# Notification.net
KiCad netlist of a schematic drawn in Altium Designer
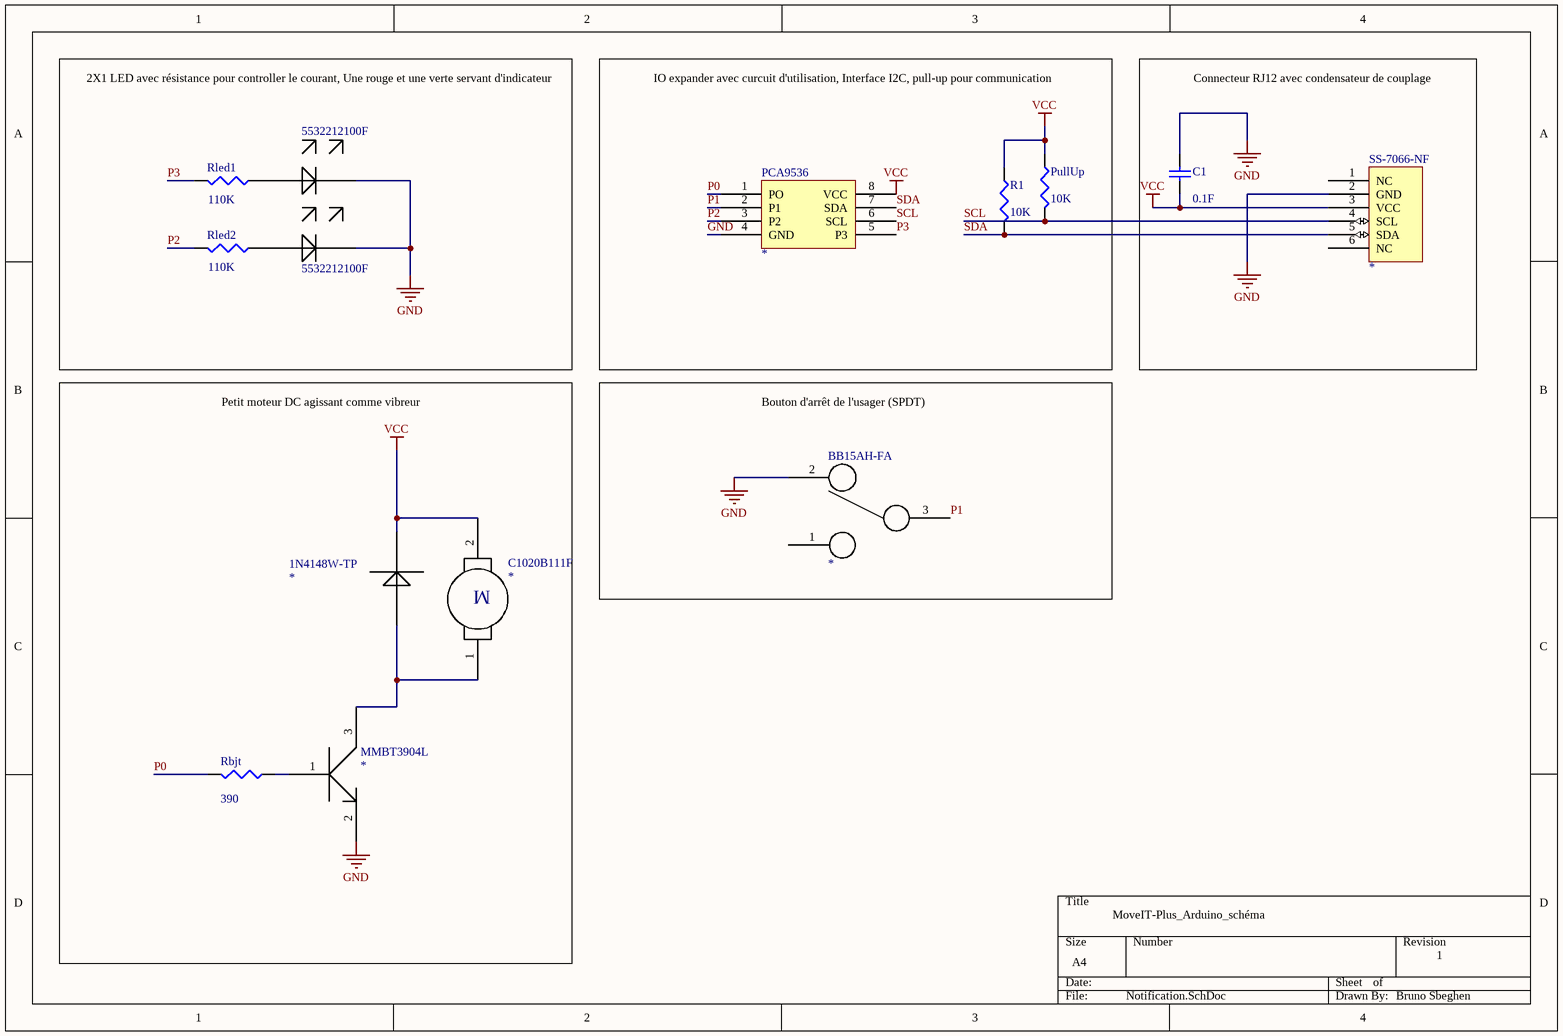
[diagram p0: Notification.SchDoc]

(export (version "E")
  (design (tool "Eeschema 10.0.6"))
  (components
    (comp (ref "1N4148W-TP")
      (value "*")
      (footprint "1N4148W")
      (description "Diode")
      (libsource (lib "MOvIT-Detect PCB") (part "1N4148W-TP"))
    )
    (comp (ref "5532212100F")
      (value "5532212100F")
      (footprint "5532212100F")
      (description "Double LED RG")
      (libsource (lib "MOvIT-Detect PCB") (part "5532212100F"))
    )
    (comp (ref "BB15AH-FA")
      (value "*")
      (footprint "BB15AH-FA")
      (description "Switch Push button ON SPDT")
      (libsource (lib "MOvIT-Detect PCB") (part "BB15AH-FA"))
    )
    (comp (ref "C1")
      (value "0.1F")
      (footprint "C0805")
      (description "Capacitor 0.1uF")
      (fields (field (name "Comment") "Cap 0.1uF") (field (name "PUBLISHER") "Altium Limited"))
      (libsource (lib "MOvIT-Detect PCB") (part "Cap 0.1uF"))
    )
    (comp (ref "C1020B111F")
      (value "*")
      (footprint "C1020B111F")
      (description "Small DC motor")
      (libsource (lib "MOvIT-Detect PCB") (part "C1020B111F"))
    )
    (comp (ref "MMBT3904L")
      (value "*")
      (footprint "MMBT3904LT3G")
      (description "BJT NPN transistor")
      (libsource (lib "MOvIT-Detect PCB") (part "MMBT3904L"))
    )
    (comp (ref "PCA9536")
      (value "*")
      (footprint "PCA9536")
      (description "IO Expander")
      (libsource (lib "MOvIT-Detect PCB") (part "PCA9536"))
    )
    (comp (ref "PullUp")
      (value "10K")
      (footprint "6-0805_N")
      (description "Resistor 10K")
      (fields (field (name "Comment") "Res 10K") (field (name "PUBLISHER") "Altium Limited"))
      (libsource (lib "MOvIT-Detect PCB") (part "Res 10K"))
    )
    (comp (ref "R1")
      (value "10K")
      (footprint "6-0805_N")
      (description "Resistor 10K")
      (fields (field (name "Comment") "Res 10K") (field (name "PUBLISHER") "Altium Limited"))
      (libsource (lib "MOvIT-Detect PCB") (part "Res 10K"))
    )
    (comp (ref "Rbjt")
      (value "390")
      (footprint "6-0805_N")
      (description "Resistor 390")
      (fields (field (name "Comment") "Res 390") (field (name "PUBLISHER") "Altium Limited"))
      (libsource (lib "MOvIT-Detect PCB") (part "Res 390"))
    )
    (comp (ref "Rled1")
      (value "110K")
      (footprint "6-0805_N")
      (description "Resistor 110")
      (fields (field (name "Comment") "Res 110") (field (name "PUBLISHER") "Altium Limited"))
      (libsource (lib "MOvIT-Detect PCB") (part "Res 110"))
    )
    (comp (ref "Rled2")
      (value "110K")
      (footprint "6-0805_N")
      (description "Resistor 110")
      (fields (field (name "Comment") "Res 110") (field (name "PUBLISHER") "Altium Limited"))
      (libsource (lib "MOvIT-Detect PCB") (part "Res 110"))
    )
    (comp (ref "SS-7066-NF")
      (value "*")
      (footprint "SS-7066-NF")
      (description "RJ12 Connector")
      (libsource (lib "MOvIT-Detect PCB") (part "SS-7066-NF"))
    )
  )
  (nets
    (net (code "1") (name "/P0") (class "Default")
      (node (ref "PCA9536") (pin "1") (pinfunction "PO_1") (pintype "passive"))
      (node (ref "Rbjt") (pin "2") (pinfunction "2_2") (pintype "passive"))
    )
    (net (code "2") (name "/P1") (class "Default")
      (node (ref "BB15AH-FA") (pin "3") (pintype "passive"))
      (node (ref "PCA9536") (pin "2") (pinfunction "P1_2") (pintype "passive"))
    )
    (net (code "3") (name "/P2") (class "Default")
      (node (ref "PCA9536") (pin "3") (pinfunction "P2_3") (pintype "passive"))
      (node (ref "Rled2") (pin "2") (pinfunction "2_2") (pintype "passive"))
    )
    (net (code "4") (name "/P3") (class "Default")
      (node (ref "PCA9536") (pin "5") (pinfunction "P3_5") (pintype "passive"))
      (node (ref "Rled1") (pin "2") (pinfunction "2_2") (pintype "passive"))
    )
    (net (code "5") (name "/SCL") (class "Default")
      (node (ref "PCA9536") (pin "6") (pinfunction "SCL_6") (pintype "passive"))
      (node (ref "PullUp") (pin "2") (pinfunction "2_2") (pintype "passive"))
      (node (ref "SS-7066-NF") (pin "4") (pinfunction "SCL_4") (pintype "bidirectional"))
    )
    (net (code "6") (name "/SDA") (class "Default")
      (node (ref "PCA9536") (pin "7") (pinfunction "SDA_7") (pintype "passive"))
      (node (ref "R1") (pin "2") (pinfunction "2_2") (pintype "passive"))
      (node (ref "SS-7066-NF") (pin "5") (pinfunction "SDA_5") (pintype "bidirectional"))
    )
    (net (code "7") (name "GND") (class "Default")
      (node (ref "5532212100F") (pin "1") (pintype "passive"))
      (node (ref "5532212100F") (pin "3") (pintype "passive"))
      (node (ref "BB15AH-FA") (pin "2") (pintype "passive"))
      (node (ref "C1") (pin "2") (pinfunction "2_2") (pintype "passive"))
      (node (ref "MMBT3904L") (pin "2") (pintype "passive"))
      (node (ref "PCA9536") (pin "4") (pinfunction "GND_4") (pintype "passive"))
      (node (ref "SS-7066-NF") (pin "2") (pinfunction "GND_2") (pintype "passive"))
    )
    (net (code "8") (name "Net-(1N4148W-TP-Pad2)") (class "Default")
      (node (ref "1N4148W-TP") (pin "2") (pintype "passive"))
      (node (ref "C1020B111F") (pin "1") (pintype "passive"))
      (node (ref "MMBT3904L") (pin "3") (pintype "passive"))
    )
    (net (code "9") (name "Net-(5532212100F-Pad2)") (class "Default")
      (node (ref "5532212100F") (pin "2") (pintype "passive"))
      (node (ref "Rled1") (pin "1") (pinfunction "1_1") (pintype "passive"))
    )
    (net (code "10") (name "Net-(5532212100F-Pad4)") (class "Default")
      (node (ref "5532212100F") (pin "4") (pintype "passive"))
      (node (ref "Rled2") (pin "1") (pinfunction "1_1") (pintype "passive"))
    )
    (net (code "11") (name "Net-(MMBT3904L-Pad1)") (class "Default")
      (node (ref "MMBT3904L") (pin "1") (pintype "passive"))
      (node (ref "Rbjt") (pin "1") (pinfunction "1_1") (pintype "passive"))
    )
    (net (code "12") (name "VCC") (class "Default")
      (node (ref "1N4148W-TP") (pin "1") (pintype "passive"))
      (node (ref "C1") (pin "1") (pinfunction "1_1") (pintype "passive"))
      (node (ref "C1020B111F") (pin "2") (pintype "passive"))
      (node (ref "PCA9536") (pin "8") (pinfunction "VCC_8") (pintype "passive"))
      (node (ref "PullUp") (pin "1") (pinfunction "1_1") (pintype "passive"))
      (node (ref "R1") (pin "1") (pinfunction "1_1") (pintype "passive"))
      (node (ref "SS-7066-NF") (pin "3") (pinfunction "VCC_3") (pintype "passive"))
    )
    (net (code "13") (name "unconnected-(BB15AH-FA-Pad1)") (class "Default")
      (node (ref "BB15AH-FA") (pin "1") (pintype "passive"))
    )
    (net (code "14") (name "unconnected-(SS-7066-NF-NC-Pad1)") (class "Default")
      (node (ref "SS-7066-NF") (pin "1") (pinfunction "NC_1") (pintype "passive"))
    )
    (net (code "15") (name "unconnected-(SS-7066-NF-NC-Pad6)") (class "Default")
      (node (ref "SS-7066-NF") (pin "6") (pinfunction "NC_6") (pintype "passive"))
    )
  )
)
